# Power_Regulators_RF_1.net
KiCad netlist of a schematic drawn in Altium Designer
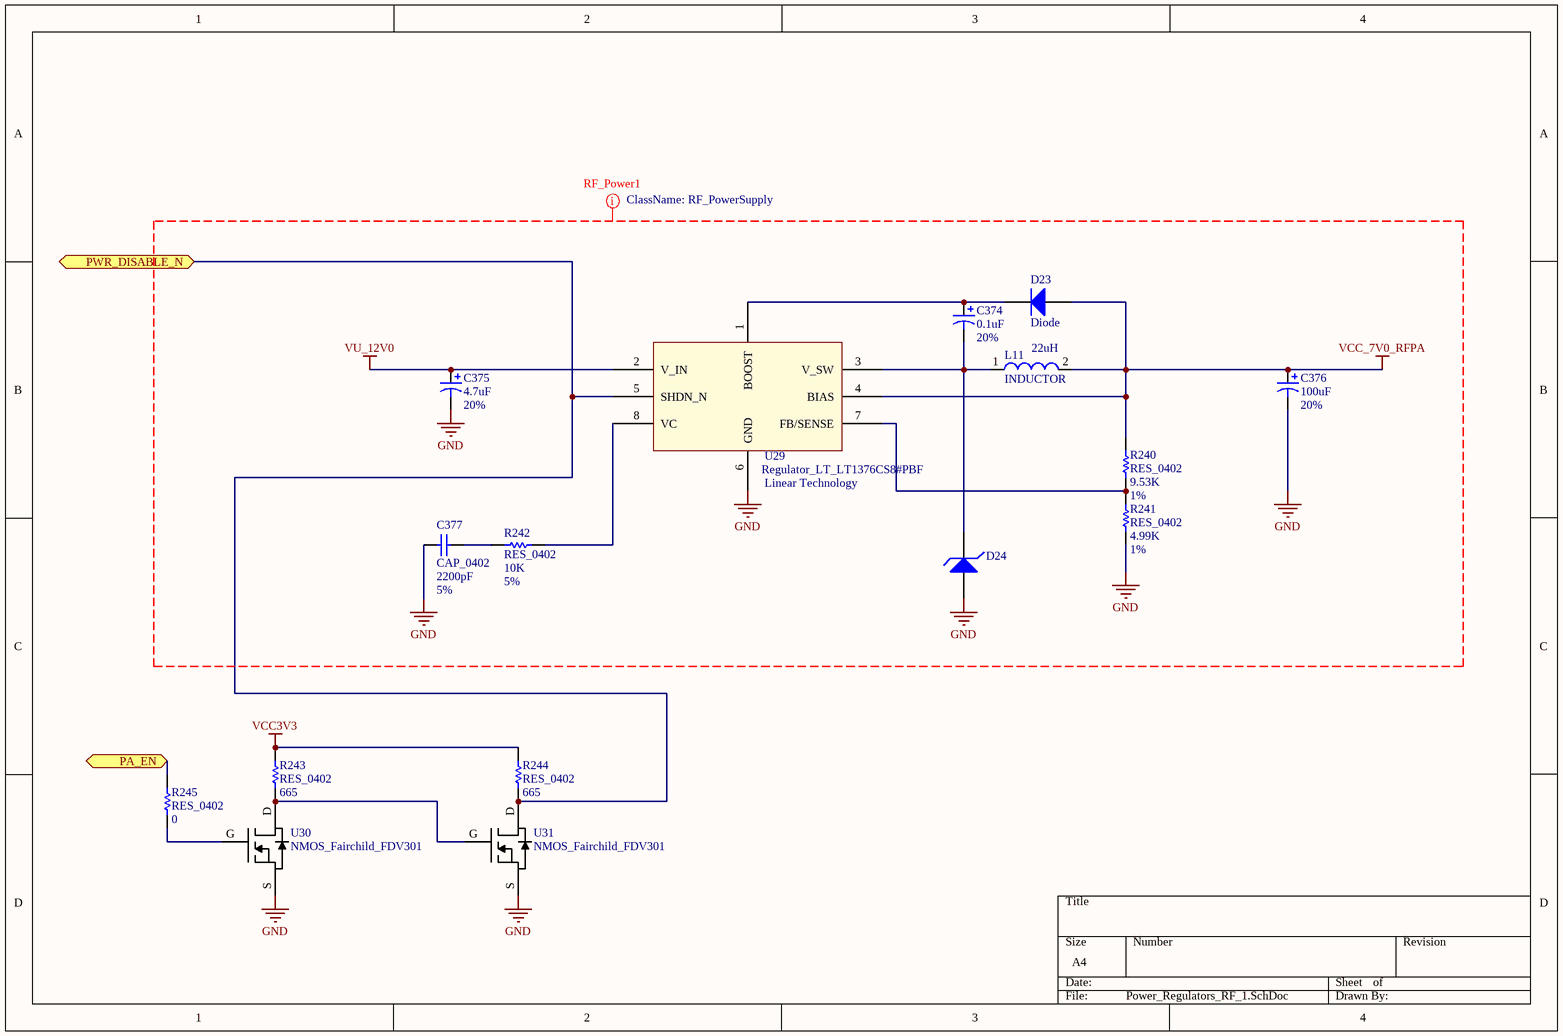
[diagram p0: Power_Regulators_RF_1.SchDoc]

(export (version "E")
  (design (tool "Eeschema 10.0.6"))
  (components
    (comp (ref "C374")
      (value "0.1uF")
      (footprint "Polarized_CAPC1206(3216)")
      (description "CAP TANT 0.1UF 35V 20% 1206")
      (fields
        (field (name "TOLERANCE") "20%")
        (field (name "PART NUMBER") "T491A104M035AT")
        (field (name "MANUFACTURER") "Kemet")
      )
      (libsource (lib "COMRAD_Database") (part "Cap Pol1"))
    )
    (comp (ref "C375")
      (value "4.7uF")
      (footprint "Polarized_CAPC1206(3216)")
      (description "CAP TANT 4.7UF 25V 20% 1206")
      (fields
        (field (name "TOLERANCE") "20%")
        (field (name "PART NUMBER") "T491A475M025AT")
        (field (name "MANUFACTURER") "Kemet")
      )
      (libsource (lib "COMRAD_Database") (part "Cap Pol1"))
    )
    (comp (ref "C376")
      (value "100uF")
      (footprint "Polarized_CAPC1210(3225)")
      (description "100uF, tantalum, 20% 10V, 1210")
      (fields
        (field (name "TOLERANCE") "20%")
        (field (name "PART NUMBER") "TLCT107M010XTA")
        (field (name "MANUFACTURER") "AVX Corporation")
      )
      (libsource (lib "COMRAD_Database") (part "Cap Pol1"))
    )
    (comp (ref "C377")
      (value "CAP_0402")
      (footprint "CAPC0402(1005)60_N")
      (description "CAP CER 2200PF 10V 5% SL 0402")
      (fields
        (field (name "ALTIUM_VALUE") "2200pF")
        (field (name "TOLERANCE") "5%")
        (field (name "PART NUMBER") "C1005SL1A222J")
        (field (name "MANUFACTURER") "TDK Corporation")
      )
      (libsource (lib "COMRAD_Database") (part "CAP_0402"))
    )
    (comp (ref "D23")
      (value "Diode")
      (footprint "Diode_DB2J31700L_2-PIN")
      (description "DIODE 30V 1A SMINI2")
      (fields
        (field (name "PART NUMBER") "DB2J31700L")
        (field (name "MANUFACTURER") "Panasonic Electronic Components - Semiconductor Products")
      )
      (libsource (lib "COMRAD_Database") (part "Diode"))
    )
    (comp (ref "D24")
      (value "Shottky Diode")
      (footprint "SchottkyDiode_SS2P2-M384A_2-PIN")
      (description "DIODE SCHOTTKY 2A 20V SMP")
      (fields
        (field (name "PART NUMBER") "SS2P2-M3/84A")
        (field (name "MANUFACTURER") "Vishay Semiconductor Diodes Division")
      )
      (libsource (lib "COMRAD_Database") (part "ShottkyDiode"))
    )
    (comp (ref "L11")
      (value "INDUCTOR")
      (footprint "Inductor_IHSM4825ER_2-PIN")
      (description "Surface Mount Inductor,22uH,1.7A")
      (fields
        (field (name "ALTIUM_VALUE") "22uH")
        (field (name "PART NUMBER") "IHSM4825ER2R0L")
        (field (name "MANUFACTURER") "Vishay Dale")
      )
      (libsource (lib "COMRAD_Database") (part "INDUCTOR"))
    )
    (comp (ref "R240")
      (value "RES_0402")
      (footprint "RESC0402(1005)_N")
      (description "RES 9.53K OHM 1/10W 1% 0402 SMD")
      (fields
        (field (name "ALTIUM_VALUE") "9.53K")
        (field (name "TOLERANCE") "1%")
        (field (name "PART NUMBER") "ERJ-2RKF9531X")
        (field (name "MANUFACTURER") "Panasonic Electronic Components")
      )
      (libsource (lib "COMRAD_Database") (part "RES_0402"))
    )
    (comp (ref "R241")
      (value "RES_0402")
      (footprint "RESC0402(1005)_N")
      (description "4.99K ohm, 1% 1/16W, 0402")
      (fields
        (field (name "ALTIUM_VALUE") "4.99K")
        (field (name "TOLERANCE") "1%")
        (field (name "PART NUMBER") "CRCW04024K99FKED")
        (field (name "MANUFACTURER") "Vishay/Dale")
      )
      (libsource (lib "COMRAD_Database") (part "RES_0402"))
    )
    (comp (ref "R242")
      (value "RES_0402")
      (footprint "RESC0402(1005)_N")
      (description "10K ohm, 5%, 1/16W, 0402")
      (fields
        (field (name "ALTIUM_VALUE") "10K")
        (field (name "TOLERANCE") "5%")
        (field (name "PART NUMBER") "RC0402JR-0710KL")
        (field (name "MANUFACTURER") "Yageo America")
      )
      (libsource (lib "COMRAD_Database") (part "RES_0402"))
    )
    (comp (ref "R243")
      (value "RES_0402")
      (footprint "RESC0402(1005)_N")
      (description "RES 665 OHM 1/10W 1% 0402 SMD")
      (fields
        (field (name "ALTIUM_VALUE") "665")
        (field (name "PART NUMBER") "ERJ-2RKF6650X")
        (field (name "MANUFACTURER") "Panasonic Electronic Components")
      )
      (libsource (lib "COMRAD_Database") (part "RES_0402"))
    )
    (comp (ref "R244")
      (value "RES_0402")
      (footprint "RESC0402(1005)_N")
      (description "RES 665 OHM 1/10W 1% 0402 SMD")
      (fields
        (field (name "ALTIUM_VALUE") "665")
        (field (name "PART NUMBER") "ERJ-2RKF6650X")
        (field (name "MANUFACTURER") "Panasonic Electronic Components")
      )
      (libsource (lib "COMRAD_Database") (part "RES_0402"))
    )
    (comp (ref "R245")
      (value "RES_0402")
      (footprint "RESC0402(1005)_N")
      (description "0.0 ohm shunt, 5%, 1/16W, 0402")
      (fields
        (field (name "ALTIUM_VALUE") "0")
        (field (name "TOLERANCE") "5%")
        (field (name "PART NUMBER") "RC0402JR-070RL")
      )
      (libsource (lib "COMRAD_Database") (part "RES_0402"))
    )
    (comp (ref "U29")
      (value "Regulator_LT_LT1376CS8#PBF")
      (footprint "LT1376CS8#PBF_8SOIC")
      (description "IC REG BUCK ADJ 1.5A 8SOIC")
      (fields (field (name "PART NUMBER") "LT1376CS8#PBF") (field (name "MANUFACTURER") "Linear Technology"))
      (libsource (lib "COMRAD_Database") (part "Regulator_LT_LT1376CS8#PBF"))
    )
    (comp (ref "U30")
      (value "NMOS_Fairchild_FDV301")
      (footprint "NMOS_Fairchild_FDV301_SOT23-3")
      (description "MOSFET N-CH 25V 220MA SOT-23")
      (fields (field (name "PART NUMBER") "FDV301N") (field (name "MANUFACTURER") "Fairchild Semiconductor"))
      (libsource (lib "COMRAD_Database") (part "NMOS_Fairchild_FDV301"))
    )
    (comp (ref "U31")
      (value "NMOS_Fairchild_FDV301")
      (footprint "NMOS_Fairchild_FDV301_SOT23-3")
      (description "MOSFET N-CH 25V 220MA SOT-23")
      (fields (field (name "PART NUMBER") "FDV301N") (field (name "MANUFACTURER") "Fairchild Semiconductor"))
      (libsource (lib "COMRAD_Database") (part "NMOS_Fairchild_FDV301"))
    )
  )
  (nets
    (net (code "1") (name "/PA_EN") (class "Default")
      (node (ref "R245") (pin "2") (pinfunction "2_2") (pintype "passive"))
    )
    (net (code "2") (name "/PWR_DISABLE_N") (class "Default")
      (node (ref "R244") (pin "1") (pinfunction "1_1") (pintype "passive"))
      (node (ref "U29") (pin "5") (pinfunction "SHDN_N_5") (pintype "passive"))
      (node (ref "U31") (pin "D") (pintype "passive"))
    )
    (net (code "3") (name "GND") (class "Default")
      (node (ref "C375") (pin "2") (pinfunction "2_2") (pintype "passive"))
      (node (ref "C376") (pin "2") (pinfunction "2_2") (pintype "passive"))
      (node (ref "C377") (pin "1") (pinfunction "1_1") (pintype "passive"))
      (node (ref "D24") (pin "2") (pinfunction "A_2") (pintype "passive"))
      (node (ref "R241") (pin "1") (pinfunction "1_1") (pintype "passive"))
      (node (ref "U29") (pin "6") (pinfunction "GND_6") (pintype "power_in"))
      (node (ref "U30") (pin "S") (pintype "passive"))
      (node (ref "U31") (pin "S") (pintype "passive"))
    )
    (net (code "4") (name "Net-(C377-Pad2)") (class "Default")
      (node (ref "C377") (pin "2") (pinfunction "2_2") (pintype "passive"))
      (node (ref "R242") (pin "1") (pinfunction "1_1") (pintype "passive"))
    )
    (net (code "5") (name "Net-(D23-K)") (class "Default")
      (node (ref "C374") (pin "1") (pinfunction "1_1") (pintype "passive"))
      (node (ref "D23") (pin "1") (pinfunction "K_1") (pintype "passive"))
      (node (ref "U29") (pin "1") (pinfunction "BOOST_1") (pintype "passive"))
    )
    (net (code "6") (name "Net-(D24-K)") (class "Default")
      (node (ref "C374") (pin "2") (pinfunction "2_2") (pintype "passive"))
      (node (ref "D24") (pin "1") (pinfunction "K_1") (pintype "passive"))
      (node (ref "L11") (pin "1") (pinfunction "1_1") (pintype "passive"))
      (node (ref "U29") (pin "3") (pinfunction "V_SW_3") (pintype "power_in"))
    )
    (net (code "7") (name "Net-(R243-Pad1)") (class "Default")
      (node (ref "R243") (pin "1") (pinfunction "1_1") (pintype "passive"))
      (node (ref "U30") (pin "D") (pintype "passive"))
      (node (ref "U31") (pin "G") (pintype "passive"))
    )
    (net (code "8") (name "Net-(R245-Pad1)") (class "Default")
      (node (ref "R245") (pin "1") (pinfunction "1_1") (pintype "passive"))
      (node (ref "U30") (pin "G") (pintype "passive"))
    )
    (net (code "9") (name "Net-(U29-FB{slash}SENSE)") (class "Default")
      (node (ref "R240") (pin "1") (pinfunction "1_1") (pintype "passive"))
      (node (ref "R241") (pin "2") (pinfunction "2_2") (pintype "passive"))
      (node (ref "U29") (pin "7") (pinfunction "FB/SENSE_7") (pintype "power_in"))
    )
    (net (code "10") (name "Net-(U29-VC)") (class "Default")
      (node (ref "R242") (pin "2") (pinfunction "2_2") (pintype "passive"))
      (node (ref "U29") (pin "8") (pinfunction "VC_8") (pintype "passive"))
    )
    (net (code "11") (name "VCC3V3") (class "Default")
      (node (ref "R243") (pin "2") (pinfunction "2_2") (pintype "passive"))
      (node (ref "R244") (pin "2") (pinfunction "2_2") (pintype "passive"))
    )
    (net (code "12") (name "VCC_7V0_RFPA") (class "Default")
      (node (ref "C376") (pin "1") (pinfunction "1_1") (pintype "passive"))
      (node (ref "D23") (pin "2") (pinfunction "A_2") (pintype "passive"))
      (node (ref "L11") (pin "2") (pinfunction "2_2") (pintype "passive"))
      (node (ref "R240") (pin "2") (pinfunction "2_2") (pintype "passive"))
      (node (ref "U29") (pin "4") (pinfunction "BIAS_4") (pintype "passive"))
    )
    (net (code "13") (name "VU_12V0") (class "Default")
      (node (ref "C375") (pin "1") (pinfunction "1_1") (pintype "passive"))
      (node (ref "U29") (pin "2") (pinfunction "V_IN_2") (pintype "power_in"))
    )
  )
)
